# Power.net
KiCad netlist of a schematic drawn in Altium Designer
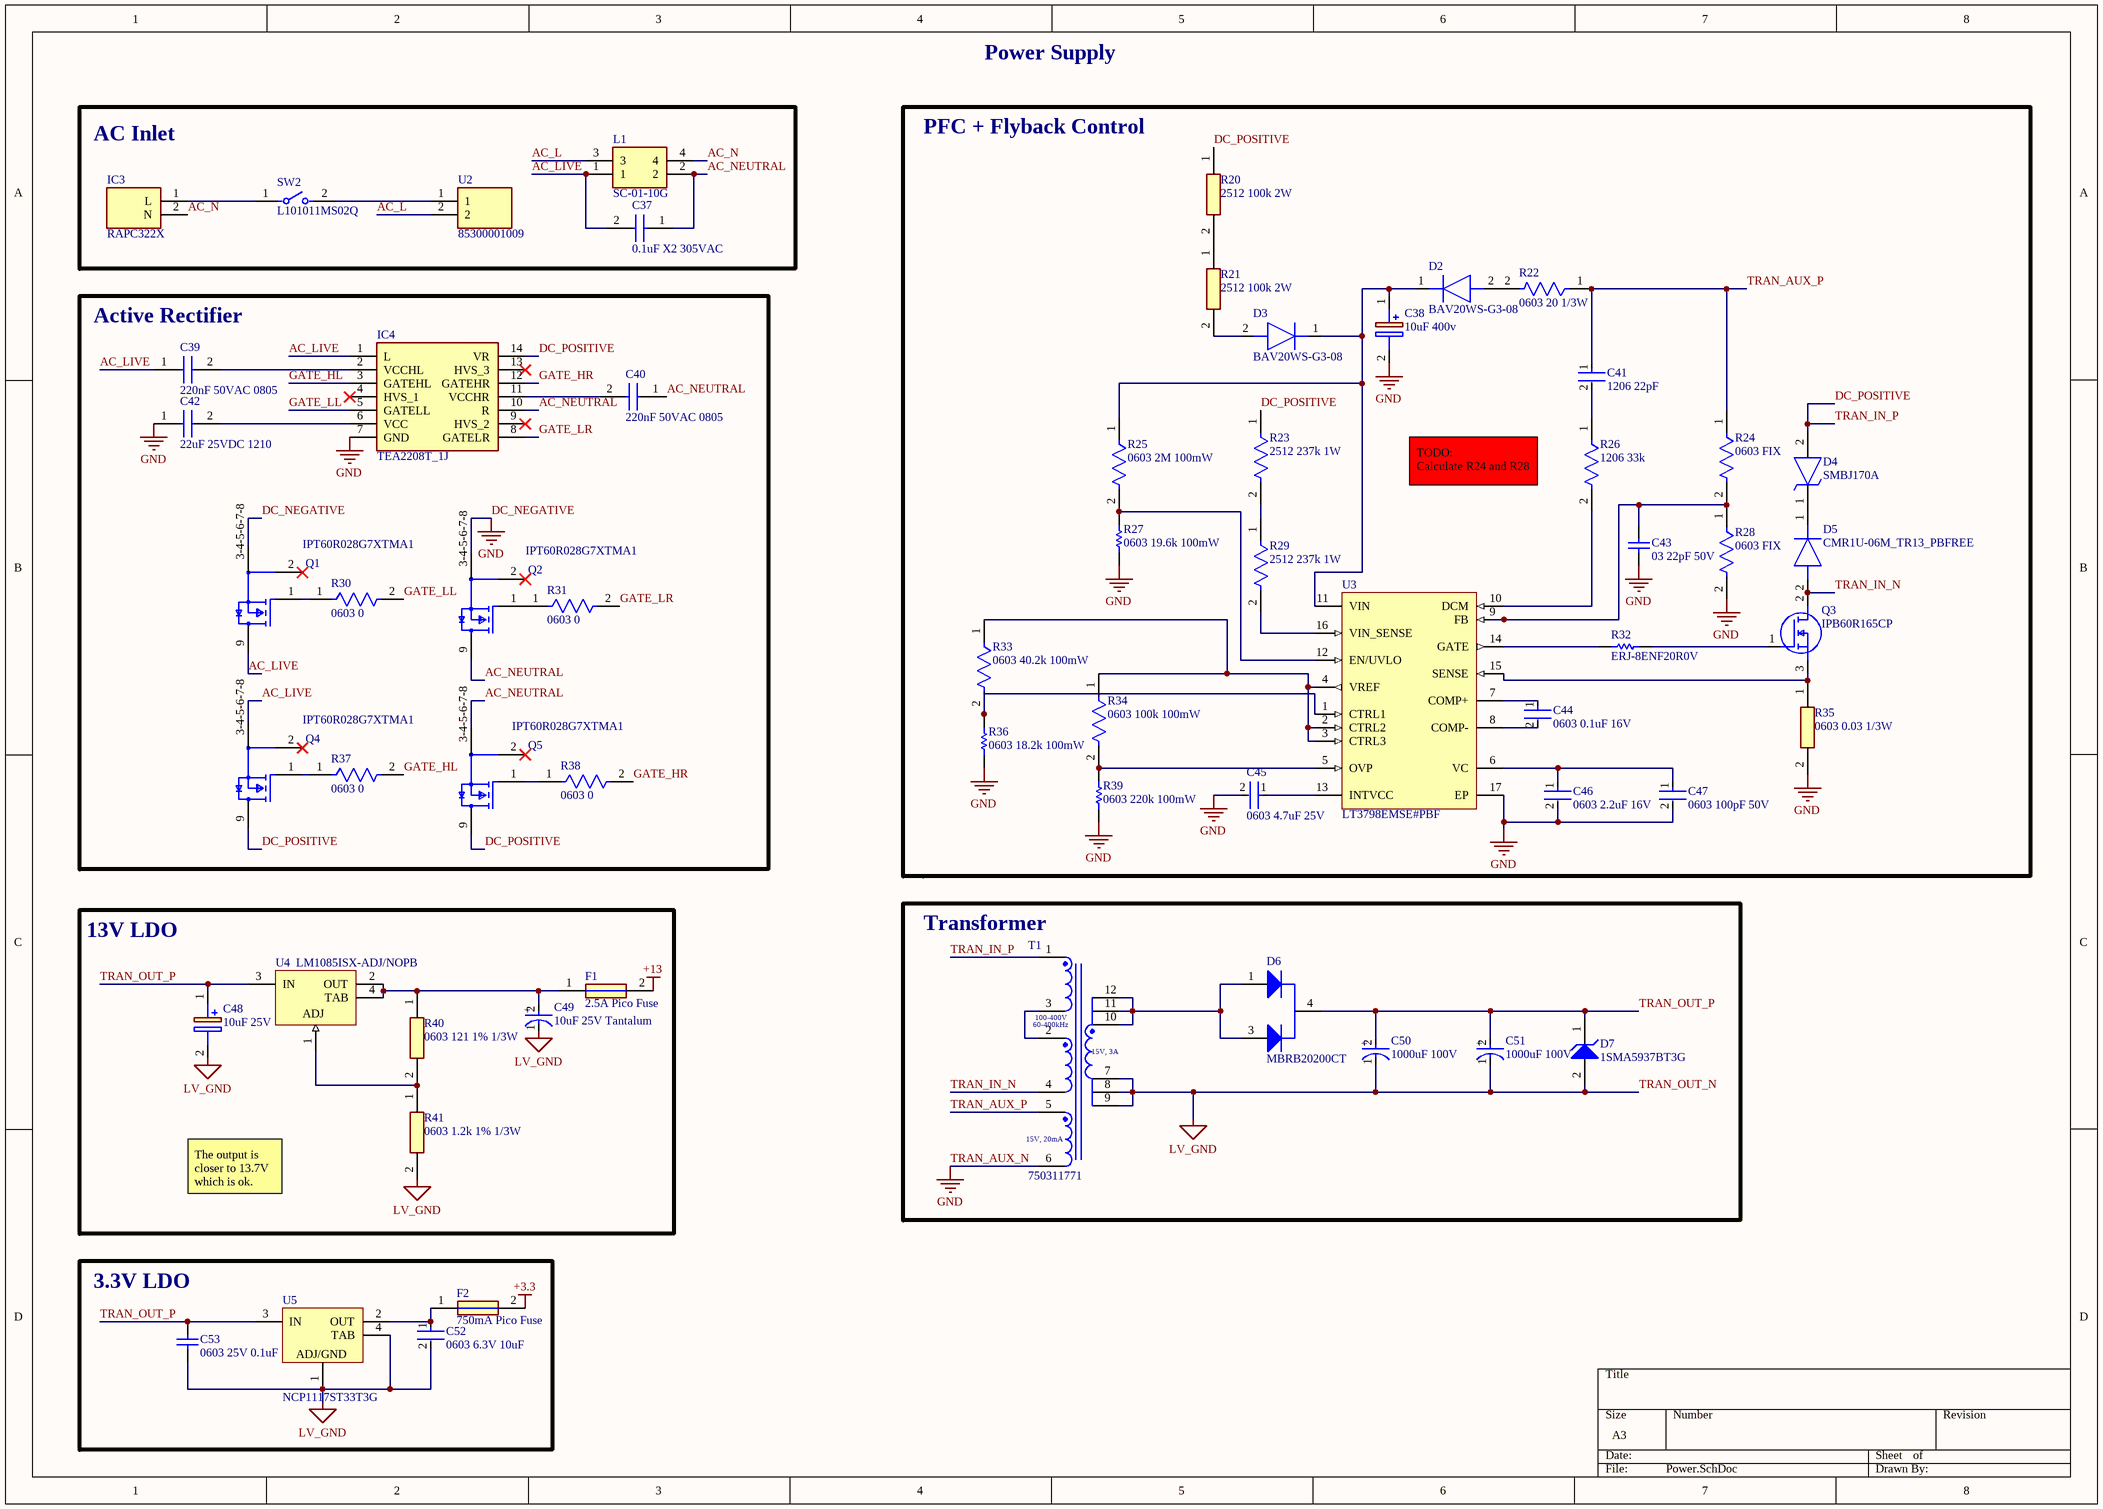
[diagram p0: Power.SchDoc]

(export (version "E")
  (design (tool "Eeschema 10.0.6"))
  (components
    (comp (ref "C37")
      (value "0.1uF X2 305VAC")
      (footprint "SamacSys:B32922C_(18_x_5)")
      (description "Capacitor")
      (fields
        (field (name "MANUFACTURER_PART_NUMBER") "B32922C3104K289")
        (field (name "MOUSER PART NUMBER") "871-B32922C3104K289")
      )
      (libsource (lib "*") (part "B32922C3104K289"))
    )
    (comp (ref "C38")
      (value "10uF 400v")
      (footprint "SamacSys:CAPPRD500W60D1025H2150")
      (description "Capacitor Polarised")
      (fields
        (field (name "MANUFACTURER_PART_NUMBER") "UCS2G100MPD1TD")
        (field (name "MOUSER PART NUMBER") "647-UCS2G100MPD1TD")
      )
      (libsource (lib "*") (part "UCS2G100MPD1TD"))
    )
    (comp (ref "C39")
      (value "220nF 50VAC 0805")
      (footprint "SamacSys:CAPC2012X145N")
      (description "Capacitor")
      (fields (field (name "MANUFACTURER_PART_NUMBER") "AC0805KFX7R9BB224"))
      (libsource (lib "*") (part "AC0805KFX7R9BB224"))
    )
    (comp (ref "C40")
      (value "220nF 50VAC 0805")
      (footprint "SamacSys:CAPC2012X145N")
      (description "Capacitor")
      (fields (field (name "MANUFACTURER_PART_NUMBER") "AC0805KFX7R9BB224"))
      (libsource (lib "*") (part "AC0805KFX7R9BB224"))
    )
    (comp (ref "C41")
      (value "1206 22pF")
      (footprint "FP-C1206C-EB-MFG")
      (description "CAP CER 22PF 100V 5% NP0 1206")
      (fields
        (field (name "MANUFACTURER PART NUMBER") "C1206C220J1GACTU")
        (field (name "MANUFACTURER") "KEMET")
      )
      (libsource (lib "Altium Content Vault") (part "b4654b650e69147ec39a6b967a45e02"))
    )
    (comp (ref "C42")
      (value "22uF 25VDC 1210")
      (footprint "SamacSys:CAPC3225X200N")
      (description "Capacitor")
      (fields
        (field (name "MANUFACTURER_PART_NUMBER") "25MU225MB23225")
        (field (name "MOUSER PART NUMBER") "232-25MU225MB23225")
      )
      (libsource (lib "*") (part "25MU225MB23225"))
    )
    (comp (ref "C43")
      (value "03 22pF 50V")
      (footprint "CAPC1608X90X35ML10T15")
      (description "Chip Capacitor, 22 pF, +/- 5%, 50 V, -55 to 125 degC, 0603 (1608 Metric), RoHS, Tape and Reel")
      (fields (field (name "MANUFACTURER") "Murata"))
      (libsource (lib "Altium Content Vault") (part "CAP-NP-2"))
    )
    (comp (ref "C44")
      (value "0603 0.1uF 16V")
      (footprint "FP-C0603C-CF-MFG")
      (description "CAP CER 0.1UF 50V X7R 0603")
      (fields (field (name "TOLERANCE") "0.1") (field (name "MANUFACTURER") "KEMET"))
      (libsource (lib "Altium Content Vault") (part "b4654b650e69147ec39a6b967a45e02"))
    )
    (comp (ref "C45")
      (value "0603 4.7uF 25V")
      (footprint "FP-GRM188-0_15-IPC_C")
      (description "Chip Multilayer Ceramic Capacitors for General Purpose, 0603, 4.7uF, X5R, 15%, 10%, 25V")
      (fields (field (name "VOLTAGE") "25V") (field (name "TOLERANCE") "10%"))
      (libsource (lib "Altium Content Vault") (part "02cd4be3c70576c341d710602a673aa"))
    )
    (comp (ref "C46")
      (value "0603 2.2uF 16V")
      (footprint "FP-C0603C225K4PACTU-MFG")
      (description "CAP CER 2.2UF 16V X5R 0603")
      (fields (field (name "TOLERANCE") "10%") (field (name "VOLTAGE") "16V"))
      (libsource (lib "Altium Content Vault") (part "b4654b650e69147ec39a6b967a45e02"))
    )
    (comp (ref "C47")
      (value "0603 100pF 50V")
      (footprint "FP-C0603C-CF-MFG")
      (description "CAP CER 100PF 50V C0G/NP0 0603")
      (fields (field (name "MANUFACTURER PART NUMBER") "C0603C101J5GACTU") (field (name "TOLERANCE") "0.05"))
      (libsource (lib "Altium Content Vault") (part "b4654b650e69147ec39a6b967a45e02"))
    )
    (comp (ref "C48")
      (value "10uF 25V")
      (footprint "SamacSys:CAPPRD200W55D500H1200")
      (description "Capacitor Polarised")
      (fields
        (field (name "MANUFACTURER_PART_NUMBER") "ECA-1EM100")
        (field (name "MOUSER PART NUMBER") "667-ECA-1EM100")
      )
      (libsource (lib "*") (part "ECA-1EM100"))
    )
    (comp (ref "C49")
      (value "10uF 25V Tantalum")
      (footprint "FP-TAJB-MFG")
      (description "10uF 25V  ±10% 2.5Ω 1210  SMD Tantalum Capacitor")
      (fields (field (name "TOLERANCE") "10%"))
      (libsource (lib "Altium Content Vault") (part "203bc49f2ac43e59fd269a8c329ed05"))
    )
    (comp (ref "C50")
      (value "1000uF 100V")
      (footprint "FP-RAD-TH-D_16_0_5-L_25_2-MFG")
      (description "Aluminum Electrolytic Capacitors (Radial Lead Type) 1000uF ±20% 50V")
      (fields (field (name "TOLERANCE") "20%"))
      (libsource (lib "Altium Content Vault") (part "203bc49f2ac43e59fd269a8c329ed05"))
    )
    (comp (ref "C51")
      (value "1000uF 100V")
      (footprint "FP-RAD-TH-D_16_0_5-L_25_2-MFG")
      (description "Aluminum Electrolytic Capacitors (Radial Lead Type) 1000uF ±20% 50V")
      (fields (field (name "TOLERANCE") "20%"))
      (libsource (lib "Altium Content Vault") (part "203bc49f2ac43e59fd269a8c329ed05"))
    )
    (comp (ref "C52")
      (value "0603 6.3V 10uF")
      (footprint "FP-GRM188-0_1-e0_2_0_55-IPC_A")
      (description "Chip Multilayer Ceramic Capacitors for General Purpose, 0603, 10uF, X5R, 15%, 20%, 6.3V")
      (fields (field (name "VOLTAGE") "6.3V") (field (name "TOLERANCE") "20%"))
      (libsource (lib "Altium Content Vault") (part "02cd4be3c70576c341d710602a673aa"))
    )
    (comp (ref "C53")
      (value "0603 25V 0.1uF")
      (footprint "CAPC1608X87X35LL15T15")
      (fields (field (name "PART NUMBER") "C0603C105K3RACTU") (field (name "MANUFACTURER") "Kemet"))
      (libsource (lib "Altium Content Vault") (part "CAP"))
    )
    (comp (ref "D2")
      (value "BAV20WS-G3-08")
      (footprint "SamacSys:SOD2713X115N")
      (description "Diode")
      (fields (field (name "MOUSER PART NUMBER") "78-BAV20WS-G3-08"))
      (libsource (lib "SamacSys") (part "BAV20WS-G3-08"))
    )
    (comp (ref "D3")
      (value "BAV20WS-G3-08")
      (footprint "SamacSys:SOD2713X115N")
      (description "Diode")
      (fields (field (name "MOUSER PART NUMBER") "78-BAV20WS-G3-08"))
      (libsource (lib "SamacSys") (part "BAV20WS-G3-08"))
    )
    (comp (ref "D4")
      (value "SMBJ170A")
      (footprint "SamacSys:DIOM5336X244N")
      (description "TVS Diode (Uni-directional)")
      (libsource (lib "SamacSys") (part "SMBJ170A"))
    )
    (comp (ref "D5")
      (value "CMR1U-06M_TR13_PBFREE")
      (footprint "SamacSys:DIOM5226X262N")
      (description "Diode")
      (fields
        (field (name "MANUFACTURER_PART_NUMBER") "CMR1U-06M TR13 PBFREE")
        (field (name "MOUSER PART NUMBER") "610-CMR1U-06M")
      )
      (libsource (lib "SamacSys") (part "CMR1U-06M_TR13_PBFREE"))
    )
    (comp (ref "D6")
      (value "MBRB20200CT")
      (footprint "ONSC-D2PAK-3-418B-04_V")
      (description "SWITCHMODE(TM) Power Rectifier, Dual Schottky Rectifiers, 3-Pin D2PAK, Tube")
      (fields (field (name "MANUFACTURER") "On Semiconductor"))
      (libsource (lib "Altium Content Vault") (part "ONSC-D-A1A3K4-3_B"))
    )
    (comp (ref "D7")
      (value "1SMA5937BT3G")
      (footprint "ONSC-SMA-2-403D-02_F_V")
      (description "1.5 W Zener Voltage Regulator, 2-Pin SMA, Pb-Free, Tape and Reel")
      (fields (field (name "MANUFACTURER") "On Semiconductor"))
      (libsource (lib "Altium Content Vault") (part "ONSC-K1A2-2"))
    )
    (comp (ref "F1")
      (value "2.5A Pico Fuse")
      (footprint "SamacSys:0251004MAT1L")
      (description "Fuse")
      (fields
        (field (name "MANUFACTURER_PART_NUMBER") "0251004.MAT1L")
        (field (name "MOUSER PART NUMBER") "576-0251004.MAT1L")
      )
      (libsource (lib "*") (part "0251004.MAT1L"))
    )
    (comp (ref "F2")
      (value "750mA Pico Fuse")
      (footprint "SamacSys:0251004MAT1L")
      (description "Fuse")
      (fields
        (field (name "MANUFACTURER_PART_NUMBER") "0251004.MAT1L")
        (field (name "MOUSER PART NUMBER") "576-0251004.MAT1L")
      )
      (libsource (lib "*") (part "0251004.MAT1L"))
    )
    (comp (ref "IC3")
      (value "RAPC322X")
      (footprint "SamacSys:RAPC322X")
      (description "Integrated Circuit")
      (fields (field (name "MOUSER PART NUMBER") "502-RAPC322X"))
      (libsource (lib "*") (part "RAPC322X"))
    )
    (comp (ref "IC4")
      (value "TEA2208T_1J")
      (footprint "SamacSys:SOIC127P600X175-14N")
      (description "Integrated Circuit")
      (fields
        (field (name "MANUFACTURER_PART_NUMBER") "TEA2208T/1J")
        (field (name "MOUSER PART NUMBER") "771-TEA2208T/1J")
      )
      (libsource (lib "*") (part "TEA2208T_1J"))
    )
    (comp (ref "L1")
      (value "SC-01-10G")
      (footprint "SamacSys:SC0110G")
      (description "Inductor")
      (fields (field (name "MOUSER PART NUMBER") "80-SC-01-10G"))
      (libsource (lib "*") (part "SC-01-10G"))
    )
    (comp (ref "Q1")
      (value "IPT60R028G7XTMA1")
      (footprint "FP-PG-HSOF-8-MFG")
      (description "MOSFET N-CH 600V 75A HSOF-8")
      (fields
        (field (name "MANUFACTURER") "Infineon")
        (field (name "OCTOPART") "https://octopart.com/ipt60r028g7xtma1-infineon-76958210")
      )
      (libsource (lib "Altium Content Vault") (part "0fd6ec2da9481abb55320df5e4c8deb"))
    )
    (comp (ref "Q2")
      (value "IPT60R028G7XTMA1")
      (footprint "FP-PG-HSOF-8-MFG")
      (description "MOSFET N-CH 600V 75A HSOF-8")
      (fields
        (field (name "MANUFACTURER") "Infineon")
        (field (name "OCTOPART") "https://octopart.com/ipt60r028g7xtma1-infineon-76958210")
      )
      (libsource (lib "Altium Content Vault") (part "0fd6ec2da9481abb55320df5e4c8deb"))
    )
    (comp (ref "Q3")
      (value "IPB60R165CP")
      (footprint "SamacSys:IPB60R165CP")
      (description "MOSFET (N-Channel)")
      (fields (field (name "MOUSER PART NUMBER") "726-IPB60R165CP"))
      (libsource (lib "SamacSys") (part "IPB60R165CP"))
    )
    (comp (ref "Q4")
      (value "IPT60R028G7XTMA1")
      (footprint "FP-PG-HSOF-8-MFG")
      (description "MOSFET N-CH 600V 75A HSOF-8")
      (fields
        (field (name "MANUFACTURER") "Infineon")
        (field (name "OCTOPART") "https://octopart.com/ipt60r028g7xtma1-infineon-76958210")
      )
      (libsource (lib "Altium Content Vault") (part "0fd6ec2da9481abb55320df5e4c8deb"))
    )
    (comp (ref "Q5")
      (value "IPT60R028G7XTMA1")
      (footprint "FP-PG-HSOF-8-MFG")
      (description "MOSFET N-CH 600V 75A HSOF-8")
      (fields
        (field (name "MANUFACTURER") "Infineon")
        (field (name "OCTOPART") "https://octopart.com/ipt60r028g7xtma1-infineon-76958210")
      )
      (libsource (lib "Altium Content Vault") (part "0fd6ec2da9481abb55320df5e4c8deb"))
    )
    (comp (ref "R20")
      (value "2512 100k 2W")
      (footprint "SamacSys:RESC6432X65N")
      (description "Resistor")
      (fields
        (field (name "MANUFACTURER_PART_NUMBER") "9-2176070-7")
        (field (name "MOUSER PART NUMBER") "279-9-2176070-7")
      )
      (libsource (lib "*") (part "9-2176070-7"))
    )
    (comp (ref "R21")
      (value "2512 100k 2W")
      (footprint "SamacSys:RESC6432X65N")
      (description "Resistor")
      (fields
        (field (name "MANUFACTURER_PART_NUMBER") "9-2176070-7")
        (field (name "MOUSER PART NUMBER") "279-9-2176070-7")
      )
      (libsource (lib "*") (part "9-2176070-7"))
    )
    (comp (ref "R22")
      (value "0603 20 1/3W")
      (footprint "FP-CRCW0603-HPe3-IPC_B")
      (description "RES Thick Film, 20Ω, 1%, 0.33W, 100ppm/°C, 0603")
      (fields (field (name "TOLERANCE") "1%"))
      (libsource (lib "Altium Content Vault") (part "1029c3af85768c4190bb7ad29bc67b5"))
    )
    (comp (ref "R23")
      (value "2512 237k 1W")
      (footprint "FP-CRCW2512-e3-IPC_B")
      (description "RES Thick Film, 237kΩ, 1%, 1W, 100ppm/°C, 2512")
      (fields (field (name "TOLERANCE") "1%"))
      (libsource (lib "Altium Content Vault") (part "1029c3af85768c4190bb7ad29bc67b5"))
    )
    (comp (ref "R24")
      (value "0603 FIX")
      (footprint "FP-CRCW0603-HPe3-MFG")
      (description "RES Thick Film, 0Ω, , 0.33W, , 0603")
      (libsource (lib "Altium Content Vault") (part "1029c3af85768c4190bb7ad29bc67b5"))
    )
    (comp (ref "R25")
      (value "0603 2M 100mW")
      (footprint "FP-CRCW0603-e3-IPC_A")
      (description "RES Thick Film, 2MΩ, 1%, 0.1W, 100ppm/°C, 0603")
      (fields (field (name "TOLERANCE") "1%"))
      (libsource (lib "Altium Content Vault") (part "1029c3af85768c4190bb7ad29bc67b5"))
    )
    (comp (ref "R26")
      (value "1206 33k")
      (footprint "FP-CRCW1206-e3-IPC_B")
      (description "RES Thick Film, 33kΩ, 1%, 0.25W, 100ppm/°C, 1206")
      (fields (field (name "TOLERANCE") "1%"))
      (libsource (lib "Altium Content Vault") (part "1029c3af85768c4190bb7ad29bc67b5"))
    )
    (comp (ref "R27")
      (value "0603 19.6k 100mW")
      (footprint "RESC1609X50X30NL10T20")
      (fields (field (name "MANUFACTURER") "Vishay Dale") (field (name "PART NUMBER") "CRCW060319K6FKEA"))
      (libsource (lib "Altium Content Vault") (part "RES"))
    )
    (comp (ref "R28")
      (value "0603 FIX")
      (footprint "FP-CRCW0603-HPe3-MFG")
      (description "RES Thick Film, 0Ω, , 0.33W, , 0603")
      (libsource (lib "Altium Content Vault") (part "1029c3af85768c4190bb7ad29bc67b5"))
    )
    (comp (ref "R29")
      (value "2512 237k 1W")
      (footprint "FP-CRCW2512-e3-IPC_B")
      (description "RES Thick Film, 237kΩ, 1%, 1W, 100ppm/°C, 2512")
      (fields (field (name "TOLERANCE") "1%"))
      (libsource (lib "Altium Content Vault") (part "1029c3af85768c4190bb7ad29bc67b5"))
    )
    (comp (ref "R30")
      (value "0603 0")
      (footprint "FP-ERJ-3GEY0R00V-MFG")
      (description "RES SMD 0 OHM JUMPER 1/10W 0603")
      (fields (field (name "TOLERANCE") "5%") (field (name "MANUFACTURER PART NUMBER") "ERJ-3GEY0R00V"))
      (libsource (lib "Altium Content Vault") (part "1029c3af85768c4190bb7ad29bc67b5"))
    )
    (comp (ref "R31")
      (value "0603 0")
      (footprint "FP-ERJ-3GEY0R00V-MFG")
      (description "RES SMD 0 OHM JUMPER 1/10W 0603")
      (fields (field (name "TOLERANCE") "5%") (field (name "MANUFACTURER PART NUMBER") "ERJ-3GEY0R00V"))
      (libsource (lib "Altium Content Vault") (part "1029c3af85768c4190bb7ad29bc67b5"))
    )
    (comp (ref "R32")
      (value "ERJ-8ENF20R0V")
      (footprint "RESC3216X70X50NL05T20")
      (fields (field (name "MANUFACTURER") "Panasonic"))
      (libsource (lib "Altium Content Vault") (part "RES"))
    )
    (comp (ref "R33")
      (value "0603 40.2k 100mW")
      (footprint "FP-RC0603-0_55-IPC_C")
      (description "RES 40.2K OHM 1% 1/10W 0603")
      (fields (field (name "TOLERANCE") "1%"))
      (libsource (lib "Altium Content Vault") (part "1029c3af85768c4190bb7ad29bc67b5"))
    )
    (comp (ref "R34")
      (value "0603 100k 100mW")
      (footprint "FP-RC0603-0_55-MFG")
      (description "RES SMD 100K OHM 1% 1/10W 0603")
      (fields (field (name "TOLERANCE") "1%"))
      (libsource (lib "Altium Content Vault") (part "1029c3af85768c4190bb7ad29bc67b5"))
    )
    (comp (ref "R35")
      (value "0603 0.03 1/3W")
      (footprint "SamacSys:ERJ3_B_BQ_BW_LW_(0603)")
      (description "Resistor")
      (fields
        (field (name "MANUFACTURER_PART_NUMBER") "ERJ-3BWFR030V")
        (field (name "MOUSER PART NUMBER") "667-ERJ-3BWFR030V")
      )
      (libsource (lib "*") (part "ERJ-3BWFR030V"))
    )
    (comp (ref "R36")
      (value "0603 18.2k 100mW")
      (footprint "RESC1608X55X30NL15T15")
      (fields (field (name "PART NUMBER") "ERJ-3EKF1822V") (field (name "MANUFACTURER") "Panasonic"))
      (libsource (lib "Altium Content Vault") (part "RES"))
    )
    (comp (ref "R37")
      (value "0603 0")
      (footprint "FP-ERJ-3GEY0R00V-MFG")
      (description "RES SMD 0 OHM JUMPER 1/10W 0603")
      (fields (field (name "TOLERANCE") "5%") (field (name "MANUFACTURER PART NUMBER") "ERJ-3GEY0R00V"))
      (libsource (lib "Altium Content Vault") (part "1029c3af85768c4190bb7ad29bc67b5"))
    )
    (comp (ref "R38")
      (value "0603 0")
      (footprint "FP-ERJ-3GEY0R00V-MFG")
      (description "RES SMD 0 OHM JUMPER 1/10W 0603")
      (fields (field (name "TOLERANCE") "5%") (field (name "MANUFACTURER PART NUMBER") "ERJ-3GEY0R00V"))
      (libsource (lib "Altium Content Vault") (part "1029c3af85768c4190bb7ad29bc67b5"))
    )
    (comp (ref "R39")
      (value "0603 220k 100mW")
      (footprint "RESC1608X55X25ML10T15")
      (description "Chip Resistor, 220 KOhm, +/- 1%, 100 mW, -55 to 155 degC, 0603 (1608 Metric), RoHS, Tape and Reel")
      (libsource (lib "Altium Content Vault") (part "RES-2"))
    )
    (comp (ref "R40")
      (value "0603 121 1% 1/3W")
      (footprint "SamacSys:RESC1608X55N")
      (description "Resistor")
      (fields
        (field (name "MANUFACTURER_PART_NUMBER") "CRCW0603121RFKEAHP")
        (field (name "MOUSER PART NUMBER") "71-CRCW0603121RFKEAH")
      )
      (libsource (lib "*") (part "CRCW0603121RFKEAHP"))
    )
    (comp (ref "R41")
      (value "0603 1.2k 1% 1/3W")
      (footprint "SamacSys:RESC1608X55N")
      (description "Resistor")
      (fields
        (field (name "MANUFACTURER_PART_NUMBER") "CRCW06031K20FKEAHP")
        (field (name "MOUSER PART NUMBER") "71-CRCW06031K20FKEAH")
      )
      (libsource (lib "*") (part "CRCW06031K20FKEAHP"))
    )
    (comp (ref "SW2")
      (value "L101011MS02Q")
      (footprint "FP-L101011MS02Q-MFG")
      (description "SWITCH SLIDE SPST 4A 125V")
      (libsource (lib "Altium Content Vault") (part "bb27bde45df87f1f469753f287ef5ae"))
    )
    (comp (ref "T1")
      (value "750311771")
      (footprint "WE-FB_EFD25")
      (libsource (lib "Altium Content Vault") (part "750311771"))
    )
    (comp (ref "U2")
      (value "85300001009")
      (footprint "SamacSys:85300001009")
      (description "Undefined or Miscellaneous")
      (fields (field (name "MOUSER PART NUMBER") "576-85300001009"))
      (libsource (lib "*") (part "85300001009"))
    )
    (comp (ref "U3")
      (value "LT3798EMSE#PBF")
      (footprint "LT-MSE-16-EDP_L")
      (fields (field (name "MANUFACTURER") "Linear Technology"))
      (libsource (lib "Altium Content Vault") (part "LT-LT3798-MSE-16"))
    )
    (comp (ref "U4")
      (value "LM1085ISX-ADJ/NOPB")
      (footprint "KTT0003B_M")
      (description "3A Low Dropout Positive Regulators, 3-pin TO-263, Pb-Free")
      (fields (field (name "MANUFACTURER") "Texas Instruments"))
      (libsource (lib "Altium Content Vault") (part "PM-REG-LM1086ADJ-SOT4"))
    )
    (comp (ref "U5")
      (value "NCP1117ST33T3G")
      (footprint "ONSC-SOT-223-4-318H-01_A_V")
      (fields (field (name "TOLERANCE") "1%"))
      (libsource (lib "Altium Content Vault") (part "ONSC-NCP1117-SOT223-4"))
    )
  )
  (nets
    (net (code "1") (name "+3.3") (class "Default")
      (node (ref "F2") (pin "2") (pinfunction "2_2") (pintype "passive"))
    )
    (net (code "2") (name "+13") (class "Default")
      (node (ref "F1") (pin "2") (pinfunction "2_2") (pintype "passive"))
    )
    (net (code "3") (name "/AC_L") (class "Default")
      (node (ref "L1") (pin "3") (pinfunction "3_3") (pintype "passive"))
      (node (ref "U2") (pin "2") (pinfunction "2_2") (pintype "passive"))
    )
    (net (code "4") (name "/AC_LIVE") (class "Default")
      (node (ref "C37") (pin "2") (pinfunction "2_2") (pintype "passive"))
      (node (ref "C39") (pin "1") (pinfunction "1_1") (pintype "passive"))
      (node (ref "IC4") (pin "1") (pinfunction "L_1") (pintype "passive"))
      (node (ref "L1") (pin "1") (pinfunction "1_1") (pintype "passive"))
      (node (ref "Q1") (pin "9") (pinfunction "Drain_9") (pintype "passive"))
      (node (ref "Q4") (pin "3-4-5-6-7-8") (pinfunction "Source_3-4-5-6-7-8") (pintype "passive"))
    )
    (net (code "5") (name "/AC_N") (class "Default")
      (node (ref "IC3") (pin "2") (pinfunction "N_2") (pintype "passive"))
      (node (ref "L1") (pin "4") (pinfunction "4_4") (pintype "passive"))
    )
    (net (code "6") (name "/AC_NEUTRAL") (class "Default")
      (node (ref "C37") (pin "1") (pinfunction "1_1") (pintype "passive"))
      (node (ref "C40") (pin "1") (pinfunction "1_1") (pintype "passive"))
      (node (ref "IC4") (pin "10") (pinfunction "R_10") (pintype "passive"))
      (node (ref "L1") (pin "2") (pinfunction "2_2") (pintype "passive"))
      (node (ref "Q2") (pin "9") (pinfunction "Drain_9") (pintype "passive"))
      (node (ref "Q5") (pin "3-4-5-6-7-8") (pinfunction "Source_3-4-5-6-7-8") (pintype "passive"))
    )
    (net (code "7") (name "/DC_POSITIVE") (class "Default")
      (node (ref "D4") (pin "2") (pinfunction "A_2") (pintype "passive"))
      (node (ref "IC4") (pin "14") (pinfunction "VR_14") (pintype "passive"))
      (node (ref "Q4") (pin "9") (pinfunction "Drain_9") (pintype "passive"))
      (node (ref "Q5") (pin "9") (pinfunction "Drain_9") (pintype "passive"))
      (node (ref "R20") (pin "1") (pinfunction "1_1") (pintype "passive"))
      (node (ref "R23") (pin "1") (pinfunction "1_1") (pintype "passive"))
      (node (ref "T1") (pin "1") (pinfunction "1_1") (pintype "passive"))
    )
    (net (code "8") (name "/GATE_HL") (class "Default")
      (node (ref "IC4") (pin "3") (pinfunction "GATEHL_3") (pintype "passive"))
      (node (ref "R37") (pin "2") (pinfunction "2_2") (pintype "passive"))
    )
    (net (code "9") (name "/GATE_HR") (class "Default")
      (node (ref "IC4") (pin "12") (pinfunction "GATEHR_12") (pintype "passive"))
      (node (ref "R38") (pin "2") (pinfunction "2_2") (pintype "passive"))
    )
    (net (code "10") (name "/GATE_LL") (class "Default")
      (node (ref "IC4") (pin "5") (pinfunction "GATELL_5") (pintype "passive"))
      (node (ref "R30") (pin "2") (pinfunction "2_2") (pintype "passive"))
    )
    (net (code "11") (name "/GATE_LR") (class "Default")
      (node (ref "IC4") (pin "8") (pinfunction "GATELR_8") (pintype "passive"))
      (node (ref "R31") (pin "2") (pinfunction "2_2") (pintype "passive"))
    )
    (net (code "12") (name "/TRAN_AUX_P") (class "Default")
      (node (ref "C41") (pin "1") (pinfunction "1_1") (pintype "passive"))
      (node (ref "R22") (pin "1") (pinfunction "1_1") (pintype "passive"))
      (node (ref "R24") (pin "1") (pinfunction "1_1") (pintype "passive"))
      (node (ref "T1") (pin "5") (pinfunction "5_5") (pintype "passive"))
    )
    (net (code "13") (name "/TRAN_IN_N") (class "Default")
      (node (ref "D5") (pin "2") (pinfunction "A_2") (pintype "passive"))
      (node (ref "Q3") (pin "2") (pinfunction "D_2") (pintype "passive"))
      (node (ref "T1") (pin "4") (pinfunction "4_4") (pintype "passive"))
    )
    (net (code "14") (name "/TRAN_OUT_P") (class "Default")
      (node (ref "C48") (pin "1") (pinfunction "+_1") (pintype "passive"))
      (node (ref "C50") (pin "2") (pinfunction "A_2") (pintype "passive"))
      (node (ref "C51") (pin "2") (pinfunction "A_2") (pintype "passive"))
      (node (ref "C53") (pin "1") (pinfunction "1_1") (pintype "passive"))
      (node (ref "D6") (pin "4") (pinfunction "K_4") (pintype "passive"))
      (node (ref "D7") (pin "1") (pinfunction "K_1") (pintype "passive"))
      (node (ref "U4") (pin "3") (pinfunction "IN_3") (pintype "power_in"))
      (node (ref "U5") (pin "3") (pinfunction "IN_3") (pintype "power_in"))
    )
    (net (code "15") (name "GND") (class "Default")
      (node (ref "C38") (pin "2") (pinfunction "-_2") (pintype "passive"))
      (node (ref "C42") (pin "1") (pinfunction "1_1") (pintype "passive"))
      (node (ref "C43") (pin "2") (pinfunction "2_2") (pintype "passive"))
      (node (ref "C45") (pin "2") (pinfunction "2_2") (pintype "passive"))
      (node (ref "C46") (pin "2") (pinfunction "2_2") (pintype "passive"))
      (node (ref "C47") (pin "2") (pinfunction "2_2") (pintype "passive"))
      (node (ref "IC4") (pin "7") (pinfunction "GND_7") (pintype "passive"))
      (node (ref "Q1") (pin "3-4-5-6-7-8") (pinfunction "Source_3-4-5-6-7-8") (pintype "passive"))
      (node (ref "Q2") (pin "3-4-5-6-7-8") (pinfunction "Source_3-4-5-6-7-8") (pintype "passive"))
      (node (ref "R27") (pin "1") (pinfunction "1_1") (pintype "passive"))
      (node (ref "R28") (pin "2") (pinfunction "2_2") (pintype "passive"))
      (node (ref "R35") (pin "2") (pinfunction "2_2") (pintype "passive"))
      (node (ref "R36") (pin "2") (pinfunction "2_2") (pintype "passive"))
      (node (ref "R39") (pin "2") (pinfunction "2_2") (pintype "passive"))
      (node (ref "T1") (pin "6") (pinfunction "6_6") (pintype "passive"))
      (node (ref "U3") (pin "17") (pinfunction "EP_17") (pintype "power_in"))
    )
    (net (code "16") (name "LV_GND") (class "Default")
      (node (ref "C48") (pin "2") (pinfunction "-_2") (pintype "passive"))
      (node (ref "C49") (pin "1") (pinfunction "C_1") (pintype "passive"))
      (node (ref "C50") (pin "1") (pinfunction "C_1") (pintype "passive"))
      (node (ref "C51") (pin "1") (pinfunction "C_1") (pintype "passive"))
      (node (ref "C52") (pin "2") (pinfunction "2_2") (pintype "passive"))
      (node (ref "C53") (pin "2") (pinfunction "2_2") (pintype "passive"))
      (node (ref "D7") (pin "2") (pinfunction "A_2") (pintype "passive"))
      (node (ref "R41") (pin "2") (pinfunction "2_2") (pintype "passive"))
      (node (ref "T1") (pin "7") (pinfunction "7_7") (pintype "passive"))
      (node (ref "T1") (pin "8") (pinfunction "8_8") (pintype "passive"))
      (node (ref "T1") (pin "9") (pinfunction "9_9") (pintype "passive"))
      (node (ref "U5") (pin "1") (pinfunction "ADJ/GND_1") (pintype "passive"))
      (node (ref "U5") (pin "4") (pinfunction "TAB_4") (pintype "passive"))
    )
    (net (code "17") (name "Net-(C38-+)") (class "Default")
      (node (ref "C38") (pin "1") (pinfunction "+_1") (pintype "passive"))
      (node (ref "D2") (pin "1") (pinfunction "K_1") (pintype "passive"))
      (node (ref "D3") (pin "1") (pinfunction "K_1") (pintype "passive"))
      (node (ref "R25") (pin "1") (pinfunction "1_1") (pintype "passive"))
      (node (ref "U3") (pin "11") (pinfunction "VIN_11") (pintype "power_in"))
    )
    (net (code "18") (name "Net-(C41-Pad2)") (class "Default")
      (node (ref "C41") (pin "2") (pinfunction "2_2") (pintype "passive"))
      (node (ref "R26") (pin "1") (pinfunction "1_1") (pintype "passive"))
    )
    (net (code "19") (name "Net-(C49-A)") (class "Default")
      (node (ref "C49") (pin "2") (pinfunction "A_2") (pintype "passive"))
      (node (ref "F1") (pin "1") (pinfunction "1_1") (pintype "passive"))
      (node (ref "R40") (pin "1") (pinfunction "1_1") (pintype "passive"))
      (node (ref "U4") (pin "2") (pinfunction "OUT_2") (pintype "power_in"))
      (node (ref "U4") (pin "4") (pinfunction "TAB_4") (pintype "power_in"))
    )
    (net (code "20") (name "Net-(D2-A)") (class "Default")
      (node (ref "D2") (pin "2") (pinfunction "A_2") (pintype "passive"))
      (node (ref "R22") (pin "2") (pinfunction "2_2") (pintype "passive"))
    )
    (net (code "21") (name "Net-(D3-A)") (class "Default")
      (node (ref "D3") (pin "2") (pinfunction "A_2") (pintype "passive"))
      (node (ref "R21") (pin "2") (pinfunction "2_2") (pintype "passive"))
    )
    (net (code "22") (name "Net-(D4-K)") (class "Default")
      (node (ref "D4") (pin "1") (pinfunction "K_1") (pintype "passive"))
      (node (ref "D5") (pin "1") (pinfunction "K_1") (pintype "passive"))
    )
    (net (code "23") (name "Net-(D6-A1)") (class "Default")
      (node (ref "D6") (pin "1") (pinfunction "A1_1") (pintype "passive"))
      (node (ref "D6") (pin "3") (pinfunction "A2_3") (pintype "passive"))
      (node (ref "T1") (pin "10") (pinfunction "10_10") (pintype "passive"))
      (node (ref "T1") (pin "11") (pinfunction "11_11") (pintype "passive"))
      (node (ref "T1") (pin "12") (pinfunction "12_12") (pintype "passive"))
    )
    (net (code "24") (name "Net-(IC3-L)") (class "Default")
      (node (ref "IC3") (pin "1") (pinfunction "L_1") (pintype "passive"))
      (node (ref "SW2") (pin "1") (pinfunction "1_1") (pintype "passive"))
    )
    (net (code "25") (name "Net-(IC4-VCC)") (class "Default")
      (node (ref "C42") (pin "2") (pinfunction "2_2") (pintype "passive"))
      (node (ref "IC4") (pin "6") (pinfunction "VCC_6") (pintype "passive"))
    )
    (net (code "26") (name "Net-(IC4-VCCHL)") (class "Default")
      (node (ref "C39") (pin "2") (pinfunction "2_2") (pintype "passive"))
      (node (ref "IC4") (pin "2") (pinfunction "VCCHL_2") (pintype "passive"))
    )
    (net (code "27") (name "Net-(IC4-VCCHR)") (class "Default")
      (node (ref "C40") (pin "2") (pinfunction "2_2") (pintype "passive"))
      (node (ref "IC4") (pin "11") (pinfunction "VCCHR_11") (pintype "passive"))
    )
    (net (code "28") (name "Net-(Q1-Gate)") (class "Default")
      (node (ref "Q1") (pin "1") (pinfunction "Gate_1") (pintype "passive"))
      (node (ref "R30") (pin "1") (pinfunction "1_1") (pintype "passive"))
    )
    (net (code "29") (name "Net-(Q2-Gate)") (class "Default")
      (node (ref "Q2") (pin "1") (pinfunction "Gate_1") (pintype "passive"))
      (node (ref "R31") (pin "1") (pinfunction "1_1") (pintype "passive"))
    )
    (net (code "30") (name "Net-(Q3-G)") (class "Default")
      (node (ref "Q3") (pin "1") (pinfunction "G_1") (pintype "passive"))
      (node (ref "R32") (pin "2") (pinfunction "2_2") (pintype "passive"))
    )
    (net (code "31") (name "Net-(Q3-S)") (class "Default")
      (node (ref "Q3") (pin "3") (pinfunction "S_3") (pintype "passive"))
      (node (ref "R35") (pin "1") (pinfunction "1_1") (pintype "passive"))
      (node (ref "U3") (pin "15") (pinfunction "SENSE_15") (pintype "input"))
    )
    (net (code "32") (name "Net-(Q4-Gate)") (class "Default")
      (node (ref "Q4") (pin "1") (pinfunction "Gate_1") (pintype "passive"))
      (node (ref "R37") (pin "1") (pinfunction "1_1") (pintype "passive"))
    )
    (net (code "33") (name "Net-(Q5-Gate)") (class "Default")
      (node (ref "Q5") (pin "1") (pinfunction "Gate_1") (pintype "passive"))
      (node (ref "R38") (pin "1") (pinfunction "1_1") (pintype "passive"))
    )
    (net (code "34") (name "Net-(R20-Pad2)") (class "Default")
      (node (ref "R20") (pin "2") (pinfunction "2_2") (pintype "passive"))
      (node (ref "R21") (pin "1") (pinfunction "1_1") (pintype "passive"))
    )
    (net (code "35") (name "Net-(R23-Pad2)") (class "Default")
      (node (ref "R23") (pin "2") (pinfunction "2_2") (pintype "passive"))
      (node (ref "R29") (pin "1") (pinfunction "1_1") (pintype "passive"))
    )
    (net (code "36") (name "Net-(SW2-Pad2)") (class "Default")
      (node (ref "SW2") (pin "2") (pinfunction "2_2") (pintype "passive"))
      (node (ref "U2") (pin "1") (pinfunction "1_1") (pintype "passive"))
    )
    (net (code "37") (name "Net-(T1-Pad2)") (class "Default")
      (node (ref "T1") (pin "2") (pinfunction "2_2") (pintype "passive"))
      (node (ref "T1") (pin "3") (pinfunction "3_3") (pintype "passive"))
    )
    (net (code "38") (name "Net-(U3-COMP+)") (class "Default")
      (node (ref "C44") (pin "1") (pinfunction "1_1") (pintype "passive"))
      (node (ref "U3") (pin "7") (pinfunction "COMP+_7") (pintype "passive"))
    )
    (net (code "39") (name "Net-(U3-COMP-)") (class "Default")
      (node (ref "C44") (pin "2") (pinfunction "2_2") (pintype "passive"))
      (node (ref "U3") (pin "8") (pinfunction "COMP-_8") (pintype "passive"))
    )
    (net (code "40") (name "Net-(U3-CTRL1)") (class "Default")
      (node (ref "R33") (pin "2") (pinfunction "2_2") (pintype "passive"))
      (node (ref "R36") (pin "1") (pinfunction "1_1") (pintype "passive"))
      (node (ref "U3") (pin "1") (pinfunction "CTRL1_1") (pintype "input"))
    )
    (net (code "41") (name "Net-(U3-CTRL2)") (class "Default")
      (node (ref "R33") (pin "1") (pinfunction "1_1") (pintype "passive"))
      (node (ref "R34") (pin "1") (pinfunction "1_1") (pintype "passive"))
      (node (ref "U3") (pin "2") (pinfunction "CTRL2_2") (pintype "input"))
      (node (ref "U3") (pin "3") (pinfunction "CTRL3_3") (pintype "input"))
      (node (ref "U3") (pin "4") (pinfunction "VREF_4") (pintype "output"))
    )
    (net (code "42") (name "Net-(U3-DCM)") (class "Default")
      (node (ref "R26") (pin "2") (pinfunction "2_2") (pintype "passive"))
      (node (ref "U3") (pin "10") (pinfunction "DCM_10") (pintype "input"))
    )
    (net (code "43") (name "Net-(U3-EN{slash}UVLO)") (class "Default")
      (node (ref "R25") (pin "2") (pinfunction "2_2") (pintype "passive"))
      (node (ref "R27") (pin "2") (pinfunction "2_2") (pintype "passive"))
      (node (ref "U3") (pin "12") (pinfunction "EN/UVLO_12") (pintype "input"))
    )
    (net (code "44") (name "Net-(U3-FB)") (class "Default")
      (node (ref "C43") (pin "1") (pinfunction "1_1") (pintype "passive"))
      (node (ref "R24") (pin "2") (pinfunction "2_2") (pintype "passive"))
      (node (ref "R28") (pin "1") (pinfunction "1_1") (pintype "passive"))
      (node (ref "U3") (pin "9") (pinfunction "FB_9") (pintype "input"))
    )
    (net (code "45") (name "Net-(U3-GATE)") (class "Default")
      (node (ref "R32") (pin "1") (pinfunction "1_1") (pintype "passive"))
      (node (ref "U3") (pin "14") (pinfunction "GATE_14") (pintype "output"))
    )
    (net (code "46") (name "Net-(U3-INTVCC)") (class "Default")
      (node (ref "C45") (pin "1") (pinfunction "1_1") (pintype "passive"))
      (node (ref "U3") (pin "13") (pinfunction "INTVCC_13") (pintype "power_in"))
    )
    (net (code "47") (name "Net-(U3-OVP)") (class "Default")
      (node (ref "R34") (pin "2") (pinfunction "2_2") (pintype "passive"))
      (node (ref "R39") (pin "1") (pinfunction "1_1") (pintype "passive"))
      (node (ref "U3") (pin "5") (pinfunction "OVP_5") (pintype "input"))
    )
    (net (code "48") (name "Net-(U3-VC)") (class "Default")
      (node (ref "C46") (pin "1") (pinfunction "1_1") (pintype "passive"))
      (node (ref "C47") (pin "1") (pinfunction "1_1") (pintype "passive"))
      (node (ref "U3") (pin "6") (pinfunction "VC_6") (pintype "passive"))
    )
    (net (code "49") (name "Net-(U3-VIN_SENSE)") (class "Default")
      (node (ref "R29") (pin "2") (pinfunction "2_2") (pintype "passive"))
      (node (ref "U3") (pin "16") (pinfunction "VIN_SENSE_16") (pintype "input"))
    )
    (net (code "50") (name "Net-(U4-ADJ)") (class "Default")
      (node (ref "R40") (pin "2") (pinfunction "2_2") (pintype "passive"))
      (node (ref "R41") (pin "1") (pinfunction "1_1") (pintype "passive"))
      (node (ref "U4") (pin "1") (pinfunction "ADJ_1") (pintype "input"))
    )
    (net (code "51") (name "Net-(U5-OUT)") (class "Default")
      (node (ref "C52") (pin "1") (pinfunction "1_1") (pintype "passive"))
      (node (ref "F2") (pin "1") (pinfunction "1_1") (pintype "passive"))
      (node (ref "U5") (pin "2") (pinfunction "OUT_2") (pintype "power_in"))
    )
    (net (code "52") (name "unconnected-(IC4-HVS_1-Pad4)") (class "Default")
      (node (ref "IC4") (pin "4") (pinfunction "HVS_1_4") (pintype "passive+no_connect"))
    )
    (net (code "53") (name "unconnected-(IC4-HVS_2-Pad9)") (class "Default")
      (node (ref "IC4") (pin "9") (pinfunction "HVS_2_9") (pintype "passive+no_connect"))
    )
    (net (code "54") (name "unconnected-(IC4-HVS_3-Pad13)") (class "Default")
      (node (ref "IC4") (pin "13") (pinfunction "HVS_3_13") (pintype "passive+no_connect"))
    )
    (net (code "55") (name "unconnected-(Q1-Driver_Source-Pad2)") (class "Default")
      (node (ref "Q1") (pin "2") (pinfunction "Driver_Source_2") (pintype "passive+no_connect"))
    )
    (net (code "56") (name "unconnected-(Q2-Driver_Source-Pad2)") (class "Default")
      (node (ref "Q2") (pin "2") (pinfunction "Driver_Source_2") (pintype "passive+no_connect"))
    )
    (net (code "57") (name "unconnected-(Q4-Driver_Source-Pad2)") (class "Default")
      (node (ref "Q4") (pin "2") (pinfunction "Driver_Source_2") (pintype "passive+no_connect"))
    )
    (net (code "58") (name "unconnected-(Q5-Driver_Source-Pad2)") (class "Default")
      (node (ref "Q5") (pin "2") (pinfunction "Driver_Source_2") (pintype "passive+no_connect"))
    )
  )
)
